# RPI_Adapter_Board.net
KiCad netlist of a schematic drawn in Altium Designer
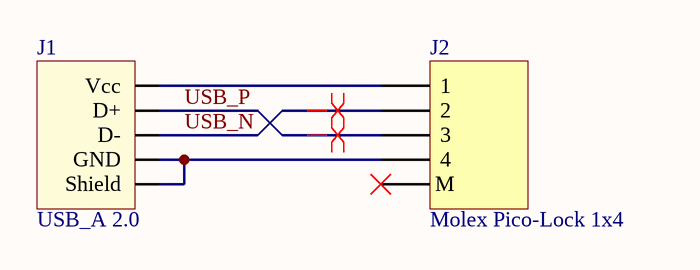
[diagram p0: RPI Adapter Board.SchDoc]

(export (version "E")
  (design (tool "Eeschema 10.0.6"))
  (components
    (comp (ref "J1")
      (value "USB_A 2.0")
      (footprint "USB_A_M_TH_V")
      (fields
        (field (name "PART NUMBER") "Kandens USB_A 2.0")
        (field (name "MANUFACTURER PART NUMBER") "AM 15.0")
      )
      (libsource (lib "FR") (part "USB_A"))
    )
    (comp (ref "J2")
      (value "Molex Pico-Lock 1x4")
      (footprint "5037630491")
      (fields (field (name "MANUFACTURER PART NUMBER") "503763-0491"))
      (libsource (lib "FR") (part "Header_1x4_M"))
    )
  )
  (nets
    (net (code "1") (name "/USB_N") (class "Default")
      (node (ref "J1") (pin "2") (pinfunction "D-_2") (pintype "passive"))
      (node (ref "J2") (pin "2") (pinfunction "2_2") (pintype "passive"))
    )
    (net (code "2") (name "/USB_P") (class "Default")
      (node (ref "J1") (pin "3") (pinfunction "D+_3") (pintype "passive"))
      (node (ref "J2") (pin "3") (pinfunction "3_3") (pintype "passive"))
    )
    (net (code "3") (name "Net-(J1-GND)") (class "Default")
      (node (ref "J1") (pin "4") (pinfunction "GND_4") (pintype "passive"))
      (node (ref "J1") (pin "5") (pinfunction "Shield_5") (pintype "passive"))
      (node (ref "J2") (pin "4") (pinfunction "4_4") (pintype "passive"))
    )
    (net (code "4") (name "Net-(J1-Vcc)") (class "Default")
      (node (ref "J1") (pin "1") (pinfunction "Vcc_1") (pintype "passive"))
      (node (ref "J2") (pin "1") (pinfunction "1_1") (pintype "passive"))
    )
    (net (code "5") (name "unconnected-(J2-M-Pad5)") (class "Default")
      (node (ref "J2") (pin "5") (pinfunction "M_5") (pintype "passive+no_connect"))
    )
  )
)
